# CONN.net
KiCad netlist of a schematic drawn in Altium Designer
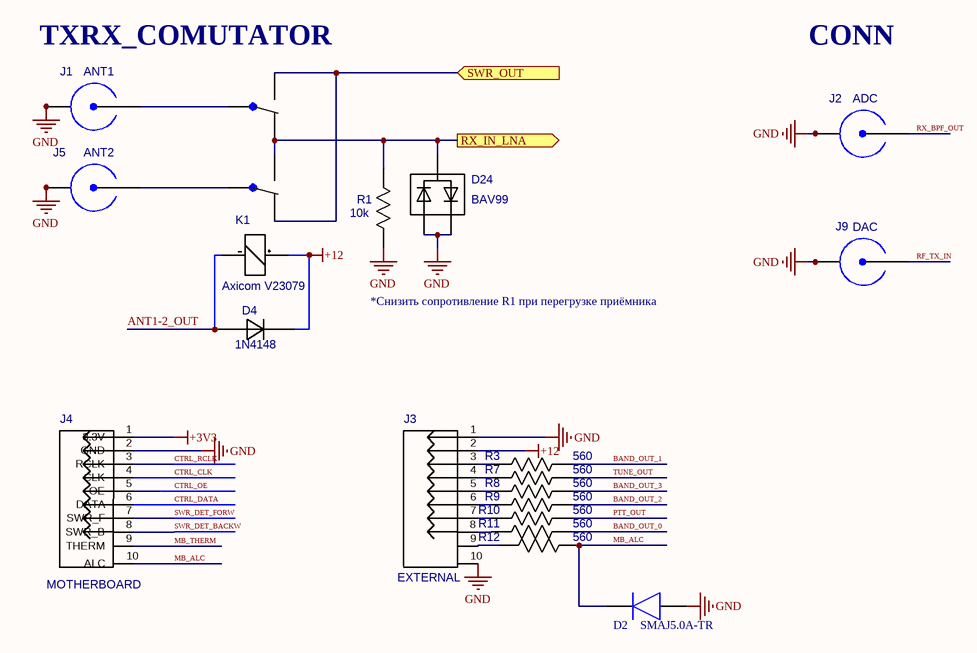
[diagram p0: CONN.SchDoc]

(export (version "E")
  (design (tool "Eeschema 10.0.6"))
  (components
    (comp (ref "D2")
      (value "SMAJ5.0A-TR")
      (footprint "SamacSys:SMBJ36CATR")
      (description "Diode")
      (fields
        (field (name "MANUFACTURER_PART_NUMBER") "SMLVT3V3")
        (field (name "MOUSER PART NUMBER") "511-SMLVT3V3")
      )
      (libsource (lib "*") (part "SMLVT3V3"))
    )
    (comp (ref "D4") (value "1N4148") (footprint "1N4148") (libsource (lib "*") (part "1N4148")))
    (comp (ref "D24") (value "BAV99") (footprint "SOT23") (libsource (lib "*") (part "BAV99")))
    (comp (ref "J1")
      (value "ANT1")
      (footprint "31-5431")
      (description "SMA")
      (libsource (lib "RF-UNIT_1") (part "31-5431"))
    )
    (comp (ref "J2")
      (value "ADC")
      (footprint "31-5431")
      (description "SMA")
      (libsource (lib "RF-UNIT_1") (part "31-5431"))
    )
    (comp (ref "J3")
      (value "EXTERNAL")
      (footprint "90131-0126")
      (description "2*5 PIN")
      (libsource (lib "RF-UNIT") (part "90131-0126"))
    )
    (comp (ref "J4")
      (value "MOTHERBOARD")
      (footprint "90131-0126")
      (description "2*5 PIN")
      (libsource (lib "") (part "90131-0126_1"))
    )
    (comp (ref "J5")
      (value "ANT2")
      (footprint "31-5431")
      (description "SMA")
      (libsource (lib "RF-UNIT_1") (part "31-5431"))
    )
    (comp (ref "J9")
      (value "DAC")
      (footprint "31-5431")
      (description "SMA")
      (libsource (lib "RF-UNIT_1") (part "31-5431"))
    )
    (comp (ref "K1")
      (value "Axicom V23079")
      (footprint "V23079")
      (libsource (lib "RF-UNIT") (part "Axicom V23079"))
    )
    (comp (ref "R1")
      (value "10k")
      (footprint "RES_1206")
      (description "RES_1206")
      (libsource (lib "*") (part "RES_1206"))
    )
    (comp (ref "R3")
      (value "560")
      (footprint "RES_0805")
      (description "RES_0805")
      (libsource (lib "*") (part "RES_0805"))
    )
    (comp (ref "R7")
      (value "560")
      (footprint "RES_0805")
      (description "RES_0805")
      (libsource (lib "*") (part "RES_0805"))
    )
    (comp (ref "R8")
      (value "560")
      (footprint "RES_0805")
      (description "RES_0805")
      (libsource (lib "*") (part "RES_0805"))
    )
    (comp (ref "R9")
      (value "560")
      (footprint "RES_0805")
      (description "RES_0805")
      (libsource (lib "*") (part "RES_0805"))
    )
    (comp (ref "R10")
      (value "560")
      (footprint "RES_0805")
      (description "RES_0805")
      (libsource (lib "*") (part "RES_0805"))
    )
    (comp (ref "R11")
      (value "560")
      (footprint "RES_0805")
      (description "RES_0805")
      (libsource (lib "*") (part "RES_0805"))
    )
    (comp (ref "R12")
      (value "560")
      (footprint "RES_0805")
      (description "RES_0805")
      (libsource (lib "*") (part "RES_0805"))
    )
  )
  (nets
    (net (code "1") (name "+3V3") (class "Default")
      (node (ref "J4") (pin "1") (pinfunction "3.3V_1") (pintype "passive"))
    )
    (net (code "2") (name "+12") (class "Default")
      (node (ref "D4") (pin "1") (pinfunction "K_1") (pintype "passive"))
      (node (ref "J3") (pin "2") (pinfunction "12V_2") (pintype "passive"))
      (node (ref "K1") (pin "1") (pinfunction "+_1") (pintype "passive"))
    )
    (net (code "4") (name "/ANT1-2_OUT") (class "Default")
      (node (ref "D4") (pin "2") (pinfunction "A_2") (pintype "passive"))
      (node (ref "K1") (pin "8") (pinfunction "-_8") (pintype "passive"))
    )
    (net (code "5") (name "/BAND_OUT_0") (class "Default")
      (node (ref "R11") (pin "2") (pinfunction "2_2") (pintype "passive"))
    )
    (net (code "6") (name "/BAND_OUT_1") (class "Default")
      (node (ref "R3") (pin "2") (pinfunction "2_2") (pintype "passive"))
    )
    (net (code "7") (name "/BAND_OUT_2") (class "Default")
      (node (ref "R9") (pin "2") (pinfunction "2_2") (pintype "passive"))
    )
    (net (code "8") (name "/BAND_OUT_3") (class "Default")
      (node (ref "R8") (pin "2") (pinfunction "2_2") (pintype "passive"))
    )
    (net (code "9") (name "/CTRL_CLK") (class "Default")
      (node (ref "J4") (pin "4") (pinfunction "CLK_4") (pintype "passive"))
    )
    (net (code "10") (name "/CTRL_DATA") (class "Default")
      (node (ref "J4") (pin "6") (pinfunction "DATA_6") (pintype "passive"))
    )
    (net (code "11") (name "/CTRL_OE") (class "Default")
      (node (ref "J4") (pin "5") (pinfunction "OE_5") (pintype "passive"))
    )
    (net (code "12") (name "/CTRL_RCLK") (class "Default")
      (node (ref "J4") (pin "3") (pinfunction "RCLK_3") (pintype "passive"))
    )
    (net (code "13") (name "/MB_ALC") (class "Default")
      (node (ref "D2") (pin "1") (pinfunction "K_1") (pintype "passive"))
      (node (ref "J4") (pin "10") (pinfunction "ALC_10") (pintype "passive"))
      (node (ref "R12") (pin "2") (pinfunction "2_2") (pintype "passive"))
    )
    (net (code "14") (name "/MB_THERM") (class "Default")
      (node (ref "J4") (pin "9") (pinfunction "THERM_9") (pintype "passive"))
    )
    (net (code "15") (name "/PTT_OUT") (class "Default")
      (node (ref "R10") (pin "2") (pinfunction "2_2") (pintype "passive"))
    )
    (net (code "16") (name "/RF_TX_IN") (class "Default")
      (node (ref "J9") (pin "5") (pinfunction "CON_5") (pintype "passive"))
    )
    (net (code "17") (name "/RX_BPF_OUT") (class "Default")
      (node (ref "J2") (pin "5") (pinfunction "CON_5") (pintype "passive"))
    )
    (net (code "18") (name "/RX_IN_LNA") (class "Default")
      (node (ref "D24") (pin "3") (pinfunction "C(D1),A(D2)_3") (pintype "passive"))
      (node (ref "K1") (pin "4") (pinfunction "S_4") (pintype "passive"))
      (node (ref "K1") (pin "7") (pinfunction "O_7") (pintype "passive"))
      (node (ref "R1") (pin "2") (pinfunction "2_2") (pintype "passive"))
    )
    (net (code "19") (name "/SWR_DET_BACKW") (class "Default")
      (node (ref "J4") (pin "8") (pinfunction "SWR_B_8") (pintype "passive"))
    )
    (net (code "20") (name "/SWR_DET_FORW") (class "Default")
      (node (ref "J4") (pin "7") (pinfunction "SWR_F_7") (pintype "passive"))
    )
    (net (code "21") (name "/SWR_OUT") (class "Default")
      (node (ref "K1") (pin "2") (pinfunction "O_2") (pintype "passive"))
      (node (ref "K1") (pin "5") (pinfunction "S_5") (pintype "passive"))
    )
    (net (code "22") (name "/TUNE_OUT") (class "Default")
      (node (ref "R7") (pin "2") (pinfunction "2_2") (pintype "passive"))
    )
    (net (code "23") (name "GND") (class "Default")
      (node (ref "D2") (pin "2") (pinfunction "A_2") (pintype "passive"))
      (node (ref "D24") (pin "1") (pinfunction "A(D1)_1") (pintype "passive"))
      (node (ref "D24") (pin "2") (pinfunction "C(D2)_2") (pintype "passive"))
      (node (ref "J1") (pin "1") (pinfunction "GND_1") (pintype "passive"))
      (node (ref "J1") (pin "2") (pinfunction "GND_2") (pintype "passive"))
      (node (ref "J1") (pin "3") (pinfunction "GND_3") (pintype "passive"))
      (node (ref "J1") (pin "4") (pinfunction "GND_4") (pintype "passive"))
      (node (ref "J2") (pin "1") (pinfunction "GND_1") (pintype "passive"))
      (node (ref "J2") (pin "2") (pinfunction "GND_2") (pintype "passive"))
      (node (ref "J2") (pin "3") (pinfunction "GND_3") (pintype "passive"))
      (node (ref "J2") (pin "4") (pinfunction "GND_4") (pintype "passive"))
      (node (ref "J3") (pin "1") (pinfunction "GND_1") (pintype "passive"))
      (node (ref "J3") (pin "10") (pinfunction "GND_10") (pintype "passive"))
      (node (ref "J4") (pin "2") (pinfunction "GND_2") (pintype "passive"))
      (node (ref "J5") (pin "1") (pinfunction "GND_1") (pintype "passive"))
      (node (ref "J5") (pin "2") (pinfunction "GND_2") (pintype "passive"))
      (node (ref "J5") (pin "3") (pinfunction "GND_3") (pintype "passive"))
      (node (ref "J5") (pin "4") (pinfunction "GND_4") (pintype "passive"))
      (node (ref "J9") (pin "1") (pinfunction "GND_1") (pintype "passive"))
      (node (ref "J9") (pin "2") (pinfunction "GND_2") (pintype "passive"))
      (node (ref "J9") (pin "3") (pinfunction "GND_3") (pintype "passive"))
      (node (ref "J9") (pin "4") (pinfunction "GND_4") (pintype "passive"))
      (node (ref "R1") (pin "1") (pinfunction "1_1") (pintype "passive"))
    )
    (net (code "24") (name "Net-(J1-CON)") (class "Default")
      (node (ref "J1") (pin "5") (pinfunction "CON_5") (pintype "passive"))
      (node (ref "K1") (pin "6") (pinfunction "P_6") (pintype "passive"))
    )
    (net (code "25") (name "Net-(J3-ALC_IN)") (class "Default")
      (node (ref "J3") (pin "9") (pinfunction "ALC_IN_9") (pintype "passive"))
      (node (ref "R12") (pin "1") (pinfunction "1_1") (pintype "passive"))
    )
    (net (code "26") (name "Net-(J3-BAND0)") (class "Default")
      (node (ref "J3") (pin "8") (pinfunction "BAND0_8") (pintype "passive"))
      (node (ref "R11") (pin "1") (pinfunction "1_1") (pintype "passive"))
    )
    (net (code "27") (name "Net-(J3-BAND1)") (class "Default")
      (node (ref "J3") (pin "3") (pinfunction "BAND1_3") (pintype "passive"))
      (node (ref "R3") (pin "1") (pinfunction "1_1") (pintype "passive"))
    )
    (net (code "28") (name "Net-(J3-BAND2)") (class "Default")
      (node (ref "J3") (pin "6") (pinfunction "BAND2_6") (pintype "passive"))
      (node (ref "R9") (pin "1") (pinfunction "1_1") (pintype "passive"))
    )
    (net (code "29") (name "Net-(J3-BAND3)") (class "Default")
      (node (ref "J3") (pin "5") (pinfunction "BAND3_5") (pintype "passive"))
      (node (ref "R8") (pin "1") (pinfunction "1_1") (pintype "passive"))
    )
    (net (code "30") (name "Net-(J3-PTT_OUT)") (class "Default")
      (node (ref "J3") (pin "7") (pinfunction "PTT_OUT_7") (pintype "passive"))
      (node (ref "R10") (pin "1") (pinfunction "1_1") (pintype "passive"))
    )
    (net (code "31") (name "Net-(J3-TUNE_OUT)") (class "Default")
      (node (ref "J3") (pin "4") (pinfunction "TUNE_OUT_4") (pintype "passive"))
      (node (ref "R7") (pin "1") (pinfunction "1_1") (pintype "passive"))
    )
    (net (code "32") (name "Net-(J5-CON)") (class "Default")
      (node (ref "J5") (pin "5") (pinfunction "CON_5") (pintype "passive"))
      (node (ref "K1") (pin "3") (pinfunction "P_3") (pintype "passive"))
    )
  )
)
